# front_wheel_encoder.net
KiCad netlist of a schematic drawn in EAGLE
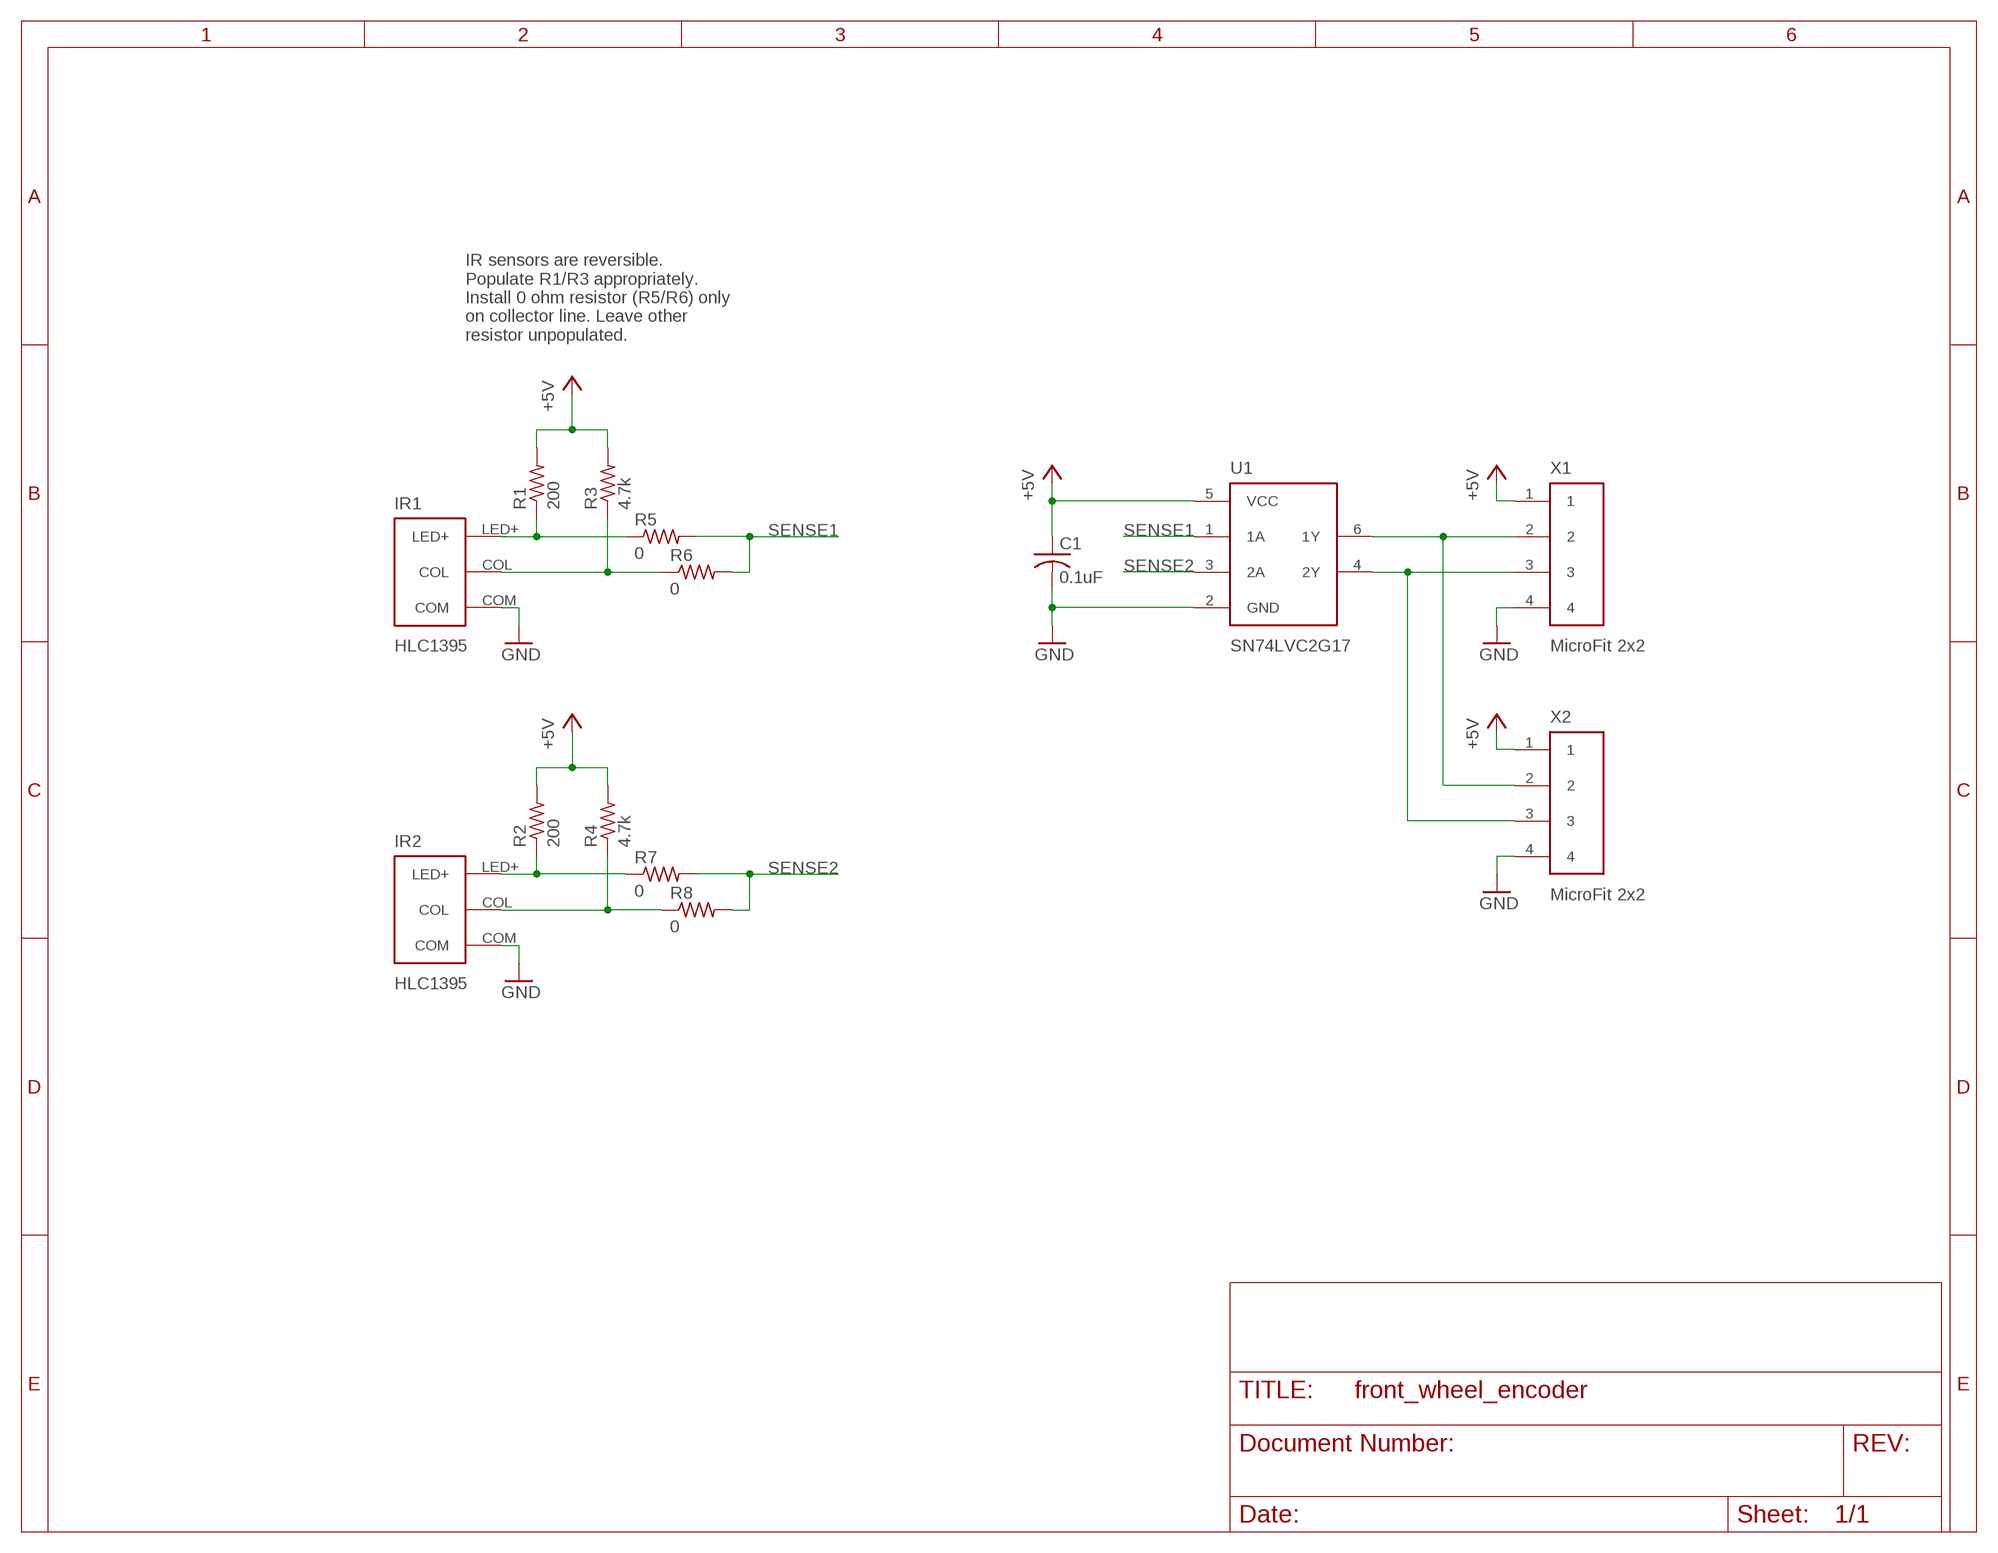
[diagram p0: schematic, sheet 1]

(export (version "E")
  (design (tool "Eeschema 10.0.6"))
  (components
    (comp (ref "C1")
      (value "0.1uF")
      (footprint "eagle-import:C0603")
      (libsource (lib "eagle-import") (part "C-USC0603"))
    )
    (comp (ref "IR1")
      (value "HLC1395")
      (footprint "eagle-import:HLC1395")
      (libsource (lib "eagle-import") (part "HLC1395"))
    )
    (comp (ref "IR2")
      (value "HLC1395")
      (footprint "eagle-import:HLC1395")
      (libsource (lib "eagle-import") (part "HLC1395"))
    )
    (comp (ref "R1")
      (value "200")
      (footprint "eagle-import:R0603")
      (libsource (lib "eagle-import") (part "R-US_R0603"))
    )
    (comp (ref "R2")
      (value "200")
      (footprint "eagle-import:R0603")
      (libsource (lib "eagle-import") (part "R-US_R0603"))
    )
    (comp (ref "R3")
      (value "4.7k")
      (footprint "eagle-import:R0603")
      (libsource (lib "eagle-import") (part "R-US_R0603"))
    )
    (comp (ref "R4")
      (value "4.7k")
      (footprint "eagle-import:R0603")
      (libsource (lib "eagle-import") (part "R-US_R0603"))
    )
    (comp (ref "R5")
      (value "0")
      (footprint "eagle-import:R0603")
      (libsource (lib "eagle-import") (part "R-US_R0603"))
    )
    (comp (ref "R6")
      (value "0")
      (footprint "eagle-import:R0603")
      (libsource (lib "eagle-import") (part "R-US_R0603"))
    )
    (comp (ref "R7")
      (value "0")
      (footprint "eagle-import:R0603")
      (libsource (lib "eagle-import") (part "R-US_R0603"))
    )
    (comp (ref "R8")
      (value "0")
      (footprint "eagle-import:R0603")
      (libsource (lib "eagle-import") (part "R-US_R0603"))
    )
    (comp (ref "U1")
      (value "SN74LVC2G17DBVR")
      (footprint "eagle-import:SOT-23-6")
      (libsource (lib "eagle-import") (part "SN74LVC2G17DBVR"))
    )
    (comp (ref "X1")
      (value "MICROFIT-2X2-SMD")
      (footprint "eagle-import:MICROFIT-2X2-0430450411")
      (libsource (lib "eagle-import") (part "MICROFIT-2X2-SMD"))
    )
    (comp (ref "X2")
      (value "MICROFIT-2X2-SMD")
      (footprint "eagle-import:MICROFIT-2X2-0430450411")
      (libsource (lib "eagle-import") (part "MICROFIT-2X2-SMD"))
    )
  )
  (nets
    (net (code "1") (name "+5V") (class "Default")
      (node (ref "C1") (pin "1") (pinfunction "1_1") (pintype "passive"))
      (node (ref "R1") (pin "2") (pinfunction "2_2") (pintype "passive"))
      (node (ref "R2") (pin "2") (pinfunction "2_2") (pintype "passive"))
      (node (ref "R3") (pin "2") (pinfunction "2_2") (pintype "passive"))
      (node (ref "R4") (pin "2") (pinfunction "2_2") (pintype "passive"))
      (node (ref "U1") (pin "5") (pinfunction "VCC_5") (pintype "power_in"))
      (node (ref "X1") (pin "1") (pinfunction "1_1") (pintype "bidirectional"))
      (node (ref "X2") (pin "1") (pinfunction "1_1") (pintype "bidirectional"))
    )
    (net (code "2") (name "/SENSE1") (class "Default")
      (node (ref "IR1") (pin "COL") (pinfunction "COL_COL") (pintype "input"))
      (node (ref "R3") (pin "1") (pinfunction "1_1") (pintype "passive"))
      (node (ref "R5") (pin "2") (pinfunction "2_2") (pintype "passive"))
      (node (ref "R6") (pin "1") (pinfunction "1_1") (pintype "passive"))
      (node (ref "R6") (pin "2") (pinfunction "2_2") (pintype "passive"))
      (node (ref "U1") (pin "1") (pinfunction "1A_1") (pintype "input"))
    )
    (net (code "3") (name "/SENSE2") (class "Default")
      (node (ref "R7") (pin "2") (pinfunction "2_2") (pintype "passive"))
      (node (ref "R8") (pin "2") (pinfunction "2_2") (pintype "passive"))
      (node (ref "U1") (pin "3") (pinfunction "2A_3") (pintype "input"))
    )
    (net (code "4") (name "GND") (class "Default")
      (node (ref "C1") (pin "2") (pinfunction "2_2") (pintype "passive"))
      (node (ref "IR1") (pin "COM") (pinfunction "COM_COM") (pintype "power_in"))
      (node (ref "IR2") (pin "COM") (pinfunction "COM_COM") (pintype "power_in"))
      (node (ref "U1") (pin "2") (pinfunction "GND_2") (pintype "power_in"))
      (node (ref "X1") (pin "4") (pinfunction "4_4") (pintype "bidirectional"))
      (node (ref "X2") (pin "4") (pinfunction "4_4") (pintype "bidirectional"))
    )
    (net (code "5") (name "Net-(IR1-PadLED+)") (class "Default")
      (node (ref "IR1") (pin "LED+") (pinfunction "LED+_LED+") (pintype "input"))
      (node (ref "R1") (pin "1") (pinfunction "1_1") (pintype "passive"))
      (node (ref "R5") (pin "1") (pinfunction "1_1") (pintype "passive"))
    )
    (net (code "6") (name "Net-(IR2-PadCOL)") (class "Default")
      (node (ref "IR2") (pin "COL") (pinfunction "COL_COL") (pintype "input"))
      (node (ref "R4") (pin "1") (pinfunction "1_1") (pintype "passive"))
      (node (ref "R8") (pin "1") (pinfunction "1_1") (pintype "passive"))
    )
    (net (code "7") (name "Net-(IR2-PadLED+)") (class "Default")
      (node (ref "IR2") (pin "LED+") (pinfunction "LED+_LED+") (pintype "input"))
      (node (ref "R2") (pin "1") (pinfunction "1_1") (pintype "passive"))
      (node (ref "R7") (pin "1") (pinfunction "1_1") (pintype "passive"))
    )
    (net (code "8") (name "Net-(U1-1Y)") (class "Default")
      (node (ref "U1") (pin "6") (pinfunction "1Y_6") (pintype "output"))
      (node (ref "X1") (pin "2") (pinfunction "2_2") (pintype "bidirectional"))
      (node (ref "X2") (pin "2") (pinfunction "2_2") (pintype "bidirectional"))
    )
    (net (code "9") (name "Net-(U1-2Y)") (class "Default")
      (node (ref "U1") (pin "4") (pinfunction "2Y_4") (pintype "output"))
      (node (ref "X1") (pin "3") (pinfunction "3_3") (pintype "bidirectional"))
      (node (ref "X2") (pin "3") (pinfunction "3_3") (pintype "bidirectional"))
    )
  )
)
